# QUADBED.net
KiCad netlist of a schematic drawn in EAGLE
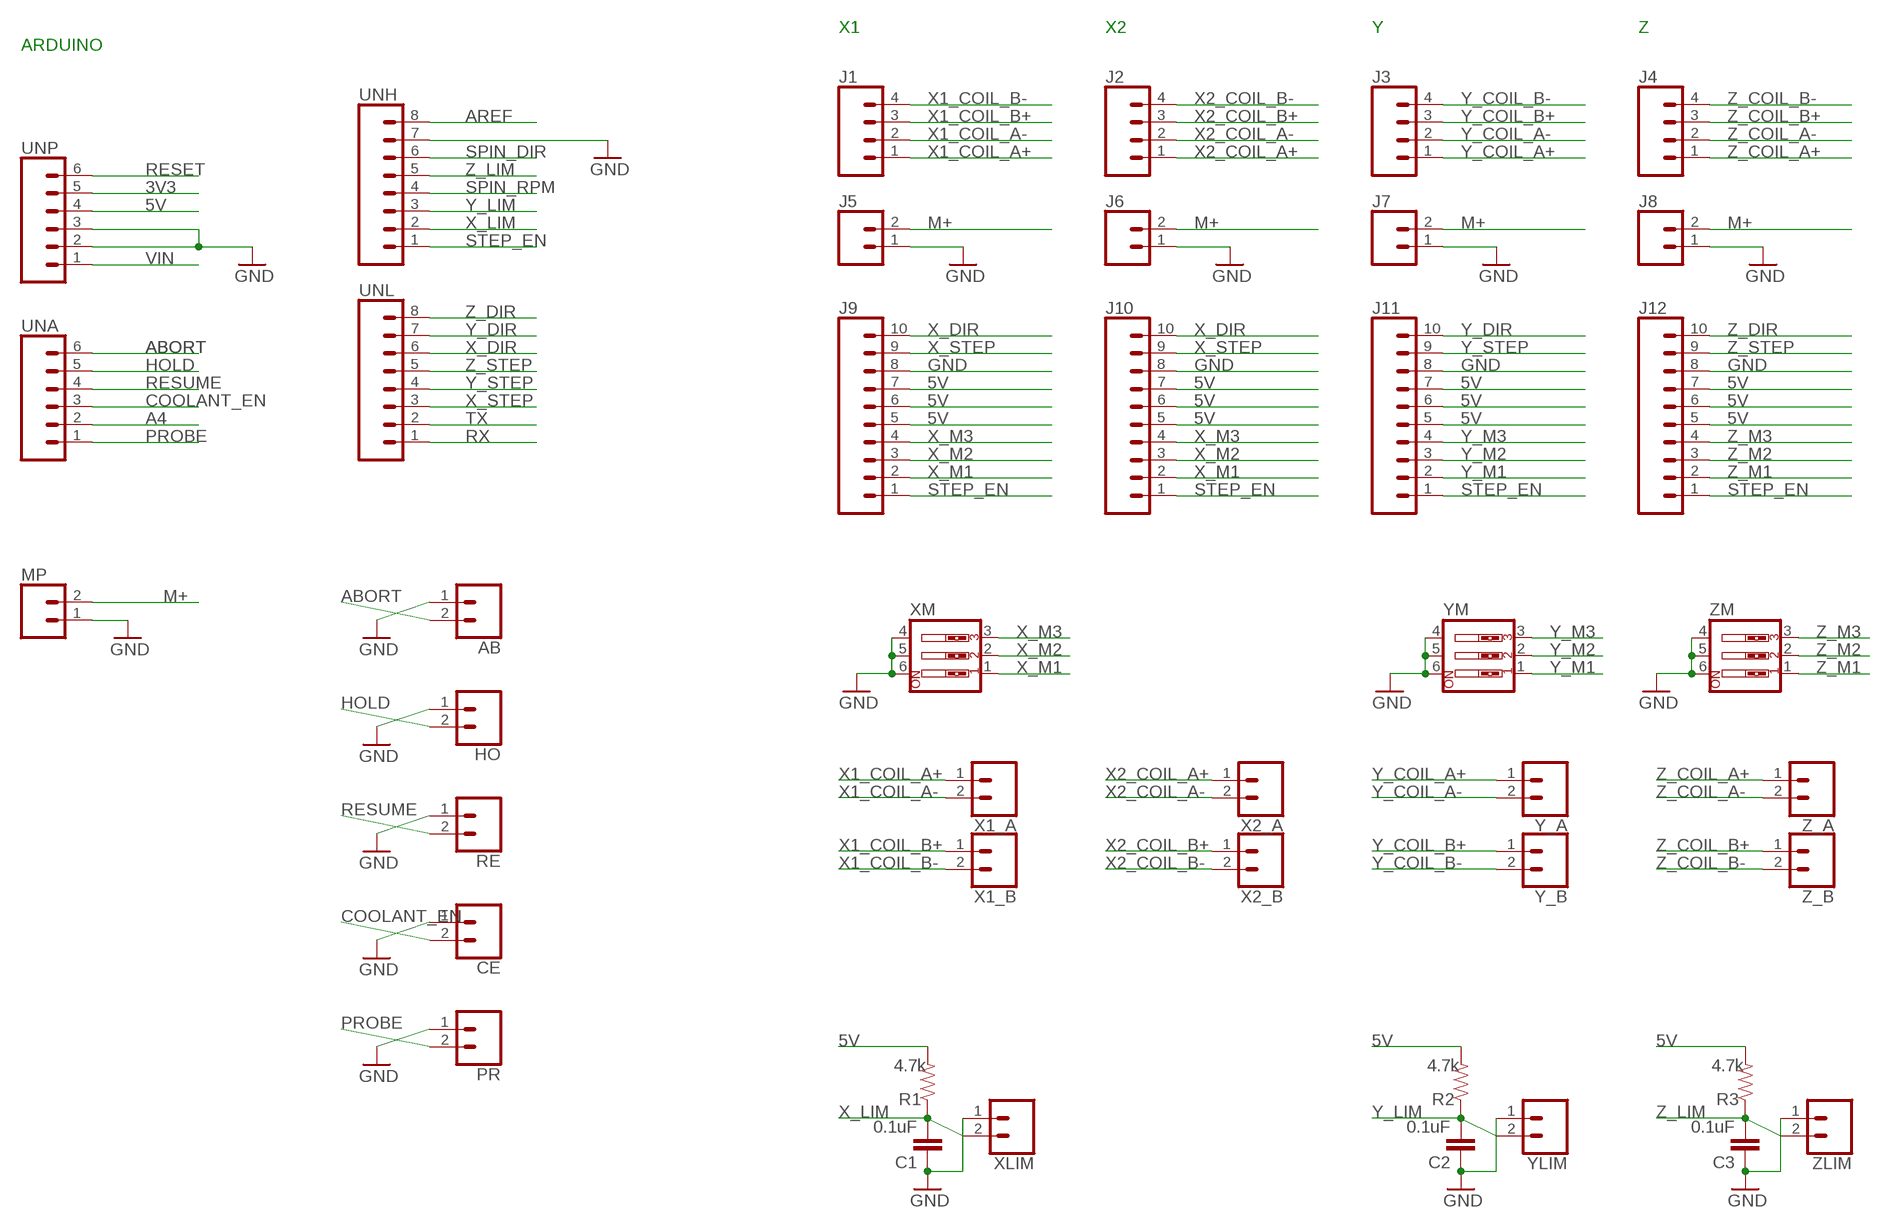
[diagram p0: schematic, sheet 1]

(export (version "E")
  (design (tool "Eeschema 10.0.6"))
  (components
    (comp (ref "AB")
      (value "CONN_023.5MM")
      (footprint "eagle-import:SCREWTERMINAL-3.5MM-2")
      (libsource (lib "eagle-import") (part "CONN_023.5MM"))
    )
    (comp (ref "C1")
      (value "0.1uF")
      (footprint "eagle-import:0603")
      (libsource (lib "eagle-import") (part "0.1UF-0603-100V-10%"))
    )
    (comp (ref "C2")
      (value "0.1uF")
      (footprint "eagle-import:0603")
      (libsource (lib "eagle-import") (part "0.1UF-0603-100V-10%"))
    )
    (comp (ref "C3")
      (value "0.1uF")
      (footprint "eagle-import:0603")
      (libsource (lib "eagle-import") (part "0.1UF-0603-100V-10%"))
    )
    (comp (ref "CE")
      (value "CONN_023.5MM")
      (footprint "eagle-import:SCREWTERMINAL-3.5MM-2")
      (libsource (lib "eagle-import") (part "CONN_023.5MM"))
    )
    (comp (ref "HO")
      (value "CONN_023.5MM")
      (footprint "eagle-import:SCREWTERMINAL-3.5MM-2")
      (libsource (lib "eagle-import") (part "CONN_023.5MM"))
    )
    (comp (ref "J1")
      (value "CONN_04")
      (footprint "eagle-import:1X04")
      (libsource (lib "eagle-import") (part "CONN_04"))
    )
    (comp (ref "J2")
      (value "CONN_04")
      (footprint "eagle-import:1X04")
      (libsource (lib "eagle-import") (part "CONN_04"))
    )
    (comp (ref "J3")
      (value "CONN_04")
      (footprint "eagle-import:1X04")
      (libsource (lib "eagle-import") (part "CONN_04"))
    )
    (comp (ref "J4")
      (value "CONN_04")
      (footprint "eagle-import:1X04")
      (libsource (lib "eagle-import") (part "CONN_04"))
    )
    (comp (ref "J5")
      (value "CONN_02")
      (footprint "eagle-import:1X02")
      (libsource (lib "eagle-import") (part "CONN_02"))
    )
    (comp (ref "J6")
      (value "CONN_02")
      (footprint "eagle-import:1X02")
      (libsource (lib "eagle-import") (part "CONN_02"))
    )
    (comp (ref "J7")
      (value "CONN_02")
      (footprint "eagle-import:1X02")
      (libsource (lib "eagle-import") (part "CONN_02"))
    )
    (comp (ref "J8")
      (value "CONN_02")
      (footprint "eagle-import:1X02")
      (libsource (lib "eagle-import") (part "CONN_02"))
    )
    (comp (ref "J9")
      (value "CONN_10\"")
      (footprint "eagle-import:1X10")
      (libsource (lib "eagle-import") (part "CONN_10{dblquote}"))
    )
    (comp (ref "J10")
      (value "CONN_10\"")
      (footprint "eagle-import:1X10")
      (libsource (lib "eagle-import") (part "CONN_10{dblquote}"))
    )
    (comp (ref "J11")
      (value "CONN_10\"")
      (footprint "eagle-import:1X10")
      (libsource (lib "eagle-import") (part "CONN_10{dblquote}"))
    )
    (comp (ref "J12")
      (value "CONN_10\"")
      (footprint "eagle-import:1X10")
      (libsource (lib "eagle-import") (part "CONN_10{dblquote}"))
    )
    (comp (ref "MP")
      (value "CONN_023.5MM")
      (footprint "eagle-import:SCREWTERMINAL-3.5MM-2")
      (fields (field (name "SPICEPREFIX") "B"))
      (libsource (lib "eagle-import") (part "CONN_023.5MM"))
    )
    (comp (ref "PR")
      (value "CONN_023.5MM")
      (footprint "eagle-import:SCREWTERMINAL-3.5MM-2")
      (libsource (lib "eagle-import") (part "CONN_023.5MM"))
    )
    (comp (ref "R1")
      (value "4.7k")
      (footprint "eagle-import:0603")
      (libsource (lib "eagle-import") (part "4.7KOHM-0603-1/10W-1%"))
    )
    (comp (ref "R2")
      (value "4.7k")
      (footprint "eagle-import:0603")
      (libsource (lib "eagle-import") (part "4.7KOHM-0603-1/10W-1%"))
    )
    (comp (ref "R3")
      (value "4.7k")
      (footprint "eagle-import:0603")
      (libsource (lib "eagle-import") (part "4.7KOHM-0603-1/10W-1%"))
    )
    (comp (ref "RE")
      (value "CONN_023.5MM")
      (footprint "eagle-import:SCREWTERMINAL-3.5MM-2")
      (libsource (lib "eagle-import") (part "CONN_023.5MM"))
    )
    (comp (ref "UNA")
      (value "CONN_06SILK_FEMALE_PTH")
      (footprint "eagle-import:1X06")
      (libsource (lib "eagle-import") (part "CONN_06SILK_FEMALE_PTH"))
    )
    (comp (ref "UNH")
      (value "CONN_08\"")
      (footprint "eagle-import:1X08")
      (libsource (lib "eagle-import") (part "CONN_08{dblquote}"))
    )
    (comp (ref "UNL")
      (value "CONN_08\"")
      (footprint "eagle-import:1X08")
      (libsource (lib "eagle-import") (part "CONN_08{dblquote}"))
    )
    (comp (ref "UNP")
      (value "CONN_06SILK_FEMALE_PTH")
      (footprint "eagle-import:1X06")
      (libsource (lib "eagle-import") (part "CONN_06SILK_FEMALE_PTH"))
    )
    (comp (ref "X1_A")
      (value "CONN_023.5MM")
      (footprint "eagle-import:SCREWTERMINAL-3.5MM-2")
      (libsource (lib "eagle-import") (part "CONN_023.5MM"))
    )
    (comp (ref "X1_B")
      (value "CONN_023.5MM")
      (footprint "eagle-import:SCREWTERMINAL-3.5MM-2")
      (libsource (lib "eagle-import") (part "CONN_023.5MM"))
    )
    (comp (ref "X2_A")
      (value "CONN_023.5MM")
      (footprint "eagle-import:SCREWTERMINAL-3.5MM-2")
      (libsource (lib "eagle-import") (part "CONN_023.5MM"))
    )
    (comp (ref "X2_B")
      (value "CONN_023.5MM")
      (footprint "eagle-import:SCREWTERMINAL-3.5MM-2")
      (libsource (lib "eagle-import") (part "CONN_023.5MM"))
    )
    (comp (ref "XLIM")
      (value "CONN_023.5MM")
      (footprint "eagle-import:SCREWTERMINAL-3.5MM-2")
      (libsource (lib "eagle-import") (part "CONN_023.5MM"))
    )
    (comp (ref "XM")
      (value "SW_DIP-3")
      (footprint "eagle-import:EDG-03")
      (libsource (lib "eagle-import") (part "SW_DIP-3"))
    )
    (comp (ref "YLIM")
      (value "CONN_023.5MM")
      (footprint "eagle-import:SCREWTERMINAL-3.5MM-2")
      (libsource (lib "eagle-import") (part "CONN_023.5MM"))
    )
    (comp (ref "YM")
      (value "SW_DIP-3")
      (footprint "eagle-import:EDG-03")
      (libsource (lib "eagle-import") (part "SW_DIP-3"))
    )
    (comp (ref "Y_A")
      (value "CONN_023.5MM")
      (footprint "eagle-import:SCREWTERMINAL-3.5MM-2")
      (libsource (lib "eagle-import") (part "CONN_023.5MM"))
    )
    (comp (ref "Y_B")
      (value "CONN_023.5MM")
      (footprint "eagle-import:SCREWTERMINAL-3.5MM-2")
      (libsource (lib "eagle-import") (part "CONN_023.5MM"))
    )
    (comp (ref "ZLIM")
      (value "CONN_023.5MM")
      (footprint "eagle-import:SCREWTERMINAL-3.5MM-2")
      (libsource (lib "eagle-import") (part "CONN_023.5MM"))
    )
    (comp (ref "ZM")
      (value "SW_DIP-3")
      (footprint "eagle-import:EDG-03")
      (libsource (lib "eagle-import") (part "SW_DIP-3"))
    )
    (comp (ref "Z_A")
      (value "CONN_023.5MM")
      (footprint "eagle-import:SCREWTERMINAL-3.5MM-2")
      (libsource (lib "eagle-import") (part "CONN_023.5MM"))
    )
    (comp (ref "Z_B")
      (value "CONN_023.5MM")
      (footprint "eagle-import:SCREWTERMINAL-3.5MM-2")
      (libsource (lib "eagle-import") (part "CONN_023.5MM"))
    )
  )
  (nets
    (net (code "1") (name "/3V3") (class "Default")
      (node (ref "UNP") (pin "5") (pinfunction "5_5") (pintype "passive"))
    )
    (net (code "2") (name "/5V") (class "Default")
      (node (ref "J10") (pin "5") (pinfunction "5_5") (pintype "passive"))
      (node (ref "J10") (pin "6") (pinfunction "6_6") (pintype "passive"))
      (node (ref "J10") (pin "7") (pinfunction "7_7") (pintype "passive"))
      (node (ref "J11") (pin "5") (pinfunction "5_5") (pintype "passive"))
      (node (ref "J11") (pin "6") (pinfunction "6_6") (pintype "passive"))
      (node (ref "J11") (pin "7") (pinfunction "7_7") (pintype "passive"))
      (node (ref "J12") (pin "5") (pinfunction "5_5") (pintype "passive"))
      (node (ref "J12") (pin "6") (pinfunction "6_6") (pintype "passive"))
      (node (ref "J12") (pin "7") (pinfunction "7_7") (pintype "passive"))
      (node (ref "J9") (pin "5") (pinfunction "5_5") (pintype "passive"))
      (node (ref "J9") (pin "6") (pinfunction "6_6") (pintype "passive"))
      (node (ref "J9") (pin "7") (pinfunction "7_7") (pintype "passive"))
      (node (ref "R1") (pin "2") (pinfunction "2_2") (pintype "passive"))
      (node (ref "R2") (pin "2") (pinfunction "2_2") (pintype "passive"))
      (node (ref "R3") (pin "2") (pinfunction "2_2") (pintype "passive"))
      (node (ref "UNP") (pin "4") (pinfunction "4_4") (pintype "passive"))
    )
    (net (code "3") (name "/A4") (class "Default")
      (node (ref "UNA") (pin "2") (pinfunction "2_2") (pintype "passive"))
    )
    (net (code "4") (name "/ABORT") (class "Default")
      (node (ref "AB") (pin "2") (pinfunction "2_2") (pintype "passive"))
      (node (ref "UNA") (pin "6") (pinfunction "6_6") (pintype "passive"))
    )
    (net (code "5") (name "/AREF") (class "Default")
      (node (ref "UNH") (pin "8") (pinfunction "8_8") (pintype "passive"))
    )
    (net (code "6") (name "/COOLANT_EN") (class "Default")
      (node (ref "CE") (pin "2") (pinfunction "2_2") (pintype "passive"))
      (node (ref "UNA") (pin "3") (pinfunction "3_3") (pintype "passive"))
    )
    (net (code "7") (name "/HOLD") (class "Default")
      (node (ref "HO") (pin "2") (pinfunction "2_2") (pintype "passive"))
      (node (ref "UNA") (pin "5") (pinfunction "5_5") (pintype "passive"))
    )
    (net (code "8") (name "/M+") (class "Default")
      (node (ref "J5") (pin "2") (pinfunction "2_2") (pintype "passive"))
      (node (ref "J6") (pin "2") (pinfunction "2_2") (pintype "passive"))
      (node (ref "J7") (pin "2") (pinfunction "2_2") (pintype "passive"))
      (node (ref "J8") (pin "2") (pinfunction "2_2") (pintype "passive"))
      (node (ref "MP") (pin "2") (pinfunction "2_2") (pintype "passive"))
    )
    (net (code "9") (name "/PROBE") (class "Default")
      (node (ref "PR") (pin "2") (pinfunction "2_2") (pintype "passive"))
      (node (ref "UNA") (pin "1") (pinfunction "1_1") (pintype "passive"))
    )
    (net (code "10") (name "/RESET") (class "Default")
      (node (ref "UNP") (pin "6") (pinfunction "6_6") (pintype "passive"))
    )
    (net (code "11") (name "/RESUME") (class "Default")
      (node (ref "RE") (pin "2") (pinfunction "2_2") (pintype "passive"))
      (node (ref "UNA") (pin "4") (pinfunction "4_4") (pintype "passive"))
    )
    (net (code "12") (name "/RX") (class "Default")
      (node (ref "UNL") (pin "1") (pinfunction "1_1") (pintype "passive"))
    )
    (net (code "13") (name "/SPIN_DIR") (class "Default")
      (node (ref "UNH") (pin "6") (pinfunction "6_6") (pintype "passive"))
    )
    (net (code "14") (name "/SPIN_RPM") (class "Default")
      (node (ref "UNH") (pin "4") (pinfunction "4_4") (pintype "passive"))
    )
    (net (code "15") (name "/STEP_EN") (class "Default")
      (node (ref "J10") (pin "1") (pinfunction "1_1") (pintype "passive"))
      (node (ref "J11") (pin "1") (pinfunction "1_1") (pintype "passive"))
      (node (ref "J12") (pin "1") (pinfunction "1_1") (pintype "passive"))
      (node (ref "J9") (pin "1") (pinfunction "1_1") (pintype "passive"))
      (node (ref "UNH") (pin "1") (pinfunction "1_1") (pintype "passive"))
    )
    (net (code "16") (name "/TX") (class "Default")
      (node (ref "UNL") (pin "2") (pinfunction "2_2") (pintype "passive"))
    )
    (net (code "17") (name "/VIN") (class "Default")
      (node (ref "UNP") (pin "1") (pinfunction "1_1") (pintype "passive"))
    )
    (net (code "18") (name "/X1_COIL_A+") (class "Default")
      (node (ref "J1") (pin "1") (pinfunction "1_1") (pintype "passive"))
      (node (ref "X1_A") (pin "1") (pinfunction "1_1") (pintype "passive"))
    )
    (net (code "19") (name "/X1_COIL_A-") (class "Default")
      (node (ref "J1") (pin "2") (pinfunction "2_2") (pintype "passive"))
      (node (ref "X1_A") (pin "2") (pinfunction "2_2") (pintype "passive"))
    )
    (net (code "20") (name "/X1_COIL_B+") (class "Default")
      (node (ref "J1") (pin "3") (pinfunction "3_3") (pintype "passive"))
      (node (ref "X1_B") (pin "1") (pinfunction "1_1") (pintype "passive"))
    )
    (net (code "21") (name "/X1_COIL_B-") (class "Default")
      (node (ref "J1") (pin "4") (pinfunction "4_4") (pintype "passive"))
      (node (ref "X1_B") (pin "2") (pinfunction "2_2") (pintype "passive"))
    )
    (net (code "22") (name "/X2_COIL_A+") (class "Default")
      (node (ref "J2") (pin "1") (pinfunction "1_1") (pintype "passive"))
      (node (ref "X2_A") (pin "1") (pinfunction "1_1") (pintype "passive"))
    )
    (net (code "23") (name "/X2_COIL_A-") (class "Default")
      (node (ref "J2") (pin "2") (pinfunction "2_2") (pintype "passive"))
      (node (ref "X2_A") (pin "2") (pinfunction "2_2") (pintype "passive"))
    )
    (net (code "24") (name "/X2_COIL_B+") (class "Default")
      (node (ref "J2") (pin "3") (pinfunction "3_3") (pintype "passive"))
      (node (ref "X2_B") (pin "1") (pinfunction "1_1") (pintype "passive"))
    )
    (net (code "25") (name "/X2_COIL_B-") (class "Default")
      (node (ref "J2") (pin "4") (pinfunction "4_4") (pintype "passive"))
      (node (ref "X2_B") (pin "2") (pinfunction "2_2") (pintype "passive"))
    )
    (net (code "26") (name "/X_DIR") (class "Default")
      (node (ref "J10") (pin "10") (pinfunction "10_10") (pintype "passive"))
      (node (ref "J9") (pin "10") (pinfunction "10_10") (pintype "passive"))
      (node (ref "UNL") (pin "6") (pinfunction "6_6") (pintype "passive"))
    )
    (net (code "27") (name "/X_LIM") (class "Default")
      (node (ref "C1") (pin "2") (pinfunction "2_2") (pintype "passive"))
      (node (ref "R1") (pin "1") (pinfunction "1_1") (pintype "passive"))
      (node (ref "UNH") (pin "2") (pinfunction "2_2") (pintype "passive"))
      (node (ref "XLIM") (pin "2") (pinfunction "2_2") (pintype "passive"))
    )
    (net (code "28") (name "/X_M1") (class "Default")
      (node (ref "J10") (pin "2") (pinfunction "2_2") (pintype "passive"))
      (node (ref "J9") (pin "2") (pinfunction "2_2") (pintype "passive"))
      (node (ref "XM") (pin "1") (pinfunction "1_1") (pintype "passive"))
    )
    (net (code "29") (name "/X_M2") (class "Default")
      (node (ref "J10") (pin "3") (pinfunction "3_3") (pintype "passive"))
      (node (ref "J9") (pin "3") (pinfunction "3_3") (pintype "passive"))
      (node (ref "XM") (pin "2") (pinfunction "2_2") (pintype "passive"))
    )
    (net (code "30") (name "/X_M3") (class "Default")
      (node (ref "J10") (pin "4") (pinfunction "4_4") (pintype "passive"))
      (node (ref "J9") (pin "4") (pinfunction "4_4") (pintype "passive"))
      (node (ref "XM") (pin "3") (pinfunction "3_3") (pintype "passive"))
    )
    (net (code "31") (name "/X_STEP") (class "Default")
      (node (ref "J10") (pin "9") (pinfunction "9_9") (pintype "passive"))
      (node (ref "J9") (pin "9") (pinfunction "9_9") (pintype "passive"))
      (node (ref "UNL") (pin "3") (pinfunction "3_3") (pintype "passive"))
    )
    (net (code "32") (name "/Y_COIL_A+") (class "Default")
      (node (ref "J3") (pin "1") (pinfunction "1_1") (pintype "passive"))
      (node (ref "Y_A") (pin "1") (pinfunction "1_1") (pintype "passive"))
    )
    (net (code "33") (name "/Y_COIL_A-") (class "Default")
      (node (ref "J3") (pin "2") (pinfunction "2_2") (pintype "passive"))
      (node (ref "Y_A") (pin "2") (pinfunction "2_2") (pintype "passive"))
    )
    (net (code "34") (name "/Y_COIL_B+") (class "Default")
      (node (ref "J3") (pin "3") (pinfunction "3_3") (pintype "passive"))
      (node (ref "Y_B") (pin "1") (pinfunction "1_1") (pintype "passive"))
    )
    (net (code "35") (name "/Y_COIL_B-") (class "Default")
      (node (ref "J3") (pin "4") (pinfunction "4_4") (pintype "passive"))
      (node (ref "Y_B") (pin "2") (pinfunction "2_2") (pintype "passive"))
    )
    (net (code "36") (name "/Y_DIR") (class "Default")
      (node (ref "J11") (pin "10") (pinfunction "10_10") (pintype "passive"))
      (node (ref "UNL") (pin "7") (pinfunction "7_7") (pintype "passive"))
    )
    (net (code "37") (name "/Y_LIM") (class "Default")
      (node (ref "C2") (pin "2") (pinfunction "2_2") (pintype "passive"))
      (node (ref "R2") (pin "1") (pinfunction "1_1") (pintype "passive"))
      (node (ref "UNH") (pin "3") (pinfunction "3_3") (pintype "passive"))
      (node (ref "YLIM") (pin "2") (pinfunction "2_2") (pintype "passive"))
    )
    (net (code "38") (name "/Y_M1") (class "Default")
      (node (ref "J11") (pin "2") (pinfunction "2_2") (pintype "passive"))
      (node (ref "YM") (pin "1") (pinfunction "1_1") (pintype "passive"))
    )
    (net (code "39") (name "/Y_M2") (class "Default")
      (node (ref "J11") (pin "3") (pinfunction "3_3") (pintype "passive"))
      (node (ref "YM") (pin "2") (pinfunction "2_2") (pintype "passive"))
    )
    (net (code "40") (name "/Y_M3") (class "Default")
      (node (ref "J11") (pin "4") (pinfunction "4_4") (pintype "passive"))
      (node (ref "YM") (pin "3") (pinfunction "3_3") (pintype "passive"))
    )
    (net (code "41") (name "/Y_STEP") (class "Default")
      (node (ref "J11") (pin "9") (pinfunction "9_9") (pintype "passive"))
      (node (ref "UNL") (pin "4") (pinfunction "4_4") (pintype "passive"))
    )
    (net (code "42") (name "/Z_COIL_A+") (class "Default")
      (node (ref "J4") (pin "1") (pinfunction "1_1") (pintype "passive"))
      (node (ref "Z_A") (pin "1") (pinfunction "1_1") (pintype "passive"))
    )
    (net (code "43") (name "/Z_COIL_A-") (class "Default")
      (node (ref "J4") (pin "2") (pinfunction "2_2") (pintype "passive"))
      (node (ref "Z_A") (pin "2") (pinfunction "2_2") (pintype "passive"))
    )
    (net (code "44") (name "/Z_COIL_B+") (class "Default")
      (node (ref "J4") (pin "3") (pinfunction "3_3") (pintype "passive"))
      (node (ref "Z_B") (pin "1") (pinfunction "1_1") (pintype "passive"))
    )
    (net (code "45") (name "/Z_COIL_B-") (class "Default")
      (node (ref "J4") (pin "4") (pinfunction "4_4") (pintype "passive"))
      (node (ref "Z_B") (pin "2") (pinfunction "2_2") (pintype "passive"))
    )
    (net (code "46") (name "/Z_DIR") (class "Default")
      (node (ref "J12") (pin "10") (pinfunction "10_10") (pintype "passive"))
      (node (ref "UNL") (pin "8") (pinfunction "8_8") (pintype "passive"))
    )
    (net (code "47") (name "/Z_LIM") (class "Default")
      (node (ref "C3") (pin "2") (pinfunction "2_2") (pintype "passive"))
      (node (ref "R3") (pin "1") (pinfunction "1_1") (pintype "passive"))
      (node (ref "UNH") (pin "5") (pinfunction "5_5") (pintype "passive"))
      (node (ref "ZLIM") (pin "2") (pinfunction "2_2") (pintype "passive"))
    )
    (net (code "48") (name "/Z_M1") (class "Default")
      (node (ref "J12") (pin "2") (pinfunction "2_2") (pintype "passive"))
      (node (ref "ZM") (pin "1") (pinfunction "1_1") (pintype "passive"))
    )
    (net (code "49") (name "/Z_M2") (class "Default")
      (node (ref "J12") (pin "3") (pinfunction "3_3") (pintype "passive"))
      (node (ref "ZM") (pin "2") (pinfunction "2_2") (pintype "passive"))
    )
    (net (code "50") (name "/Z_M3") (class "Default")
      (node (ref "J12") (pin "4") (pinfunction "4_4") (pintype "passive"))
      (node (ref "ZM") (pin "3") (pinfunction "3_3") (pintype "passive"))
    )
    (net (code "51") (name "/Z_STEP") (class "Default")
      (node (ref "J12") (pin "9") (pinfunction "9_9") (pintype "passive"))
      (node (ref "UNL") (pin "5") (pinfunction "5_5") (pintype "passive"))
    )
    (net (code "52") (name "GND") (class "Default")
      (node (ref "AB") (pin "1") (pinfunction "1_1") (pintype "passive"))
      (node (ref "C1") (pin "1") (pinfunction "1_1") (pintype "passive"))
      (node (ref "C2") (pin "1") (pinfunction "1_1") (pintype "passive"))
      (node (ref "C3") (pin "1") (pinfunction "1_1") (pintype "passive"))
      (node (ref "CE") (pin "1") (pinfunction "1_1") (pintype "passive"))
      (node (ref "HO") (pin "1") (pinfunction "1_1") (pintype "passive"))
      (node (ref "J10") (pin "8") (pinfunction "8_8") (pintype "passive"))
      (node (ref "J11") (pin "8") (pinfunction "8_8") (pintype "passive"))
      (node (ref "J12") (pin "8") (pinfunction "8_8") (pintype "passive"))
      (node (ref "J5") (pin "1") (pinfunction "1_1") (pintype "passive"))
      (node (ref "J6") (pin "1") (pinfunction "1_1") (pintype "passive"))
      (node (ref "J7") (pin "1") (pinfunction "1_1") (pintype "passive"))
      (node (ref "J8") (pin "1") (pinfunction "1_1") (pintype "passive"))
      (node (ref "J9") (pin "8") (pinfunction "8_8") (pintype "passive"))
      (node (ref "MP") (pin "1") (pinfunction "1_1") (pintype "passive"))
      (node (ref "PR") (pin "1") (pinfunction "1_1") (pintype "passive"))
      (node (ref "RE") (pin "1") (pinfunction "1_1") (pintype "passive"))
      (node (ref "UNH") (pin "7") (pinfunction "7_7") (pintype "passive"))
      (node (ref "UNP") (pin "2") (pinfunction "2_2") (pintype "passive"))
      (node (ref "UNP") (pin "3") (pinfunction "3_3") (pintype "passive"))
      (node (ref "XLIM") (pin "1") (pinfunction "1_1") (pintype "passive"))
      (node (ref "XM") (pin "4") (pinfunction "4_4") (pintype "passive"))
      (node (ref "XM") (pin "5") (pinfunction "5_5") (pintype "passive"))
      (node (ref "XM") (pin "6") (pinfunction "6_6") (pintype "passive"))
      (node (ref "YLIM") (pin "1") (pinfunction "1_1") (pintype "passive"))
      (node (ref "YM") (pin "4") (pinfunction "4_4") (pintype "passive"))
      (node (ref "YM") (pin "5") (pinfunction "5_5") (pintype "passive"))
      (node (ref "YM") (pin "6") (pinfunction "6_6") (pintype "passive"))
      (node (ref "ZLIM") (pin "1") (pinfunction "1_1") (pintype "passive"))
      (node (ref "ZM") (pin "4") (pinfunction "4_4") (pintype "passive"))
      (node (ref "ZM") (pin "5") (pinfunction "5_5") (pintype "passive"))
      (node (ref "ZM") (pin "6") (pinfunction "6_6") (pintype "passive"))
    )
  )
)
